# esp-proto-board.net
KiCad netlist of a schematic drawn in EAGLE
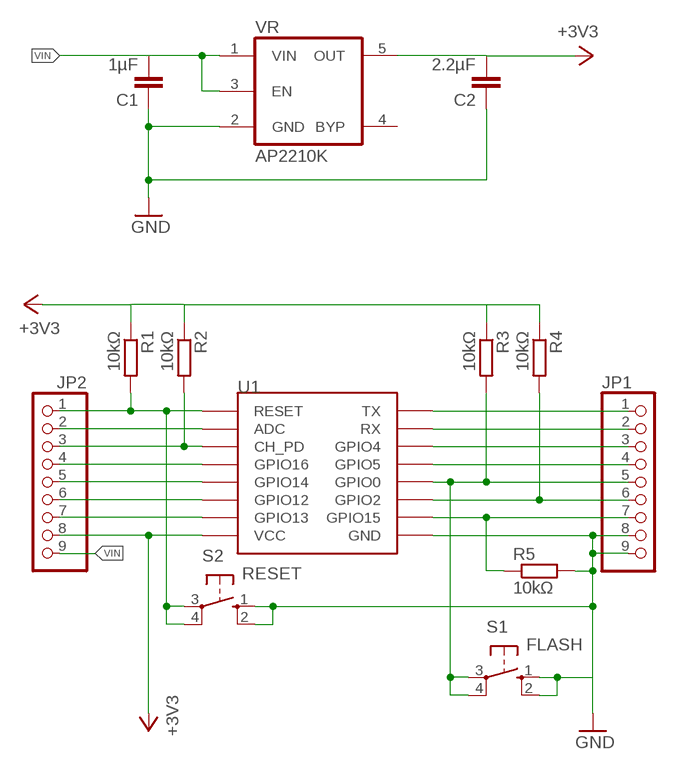
[diagram p0: schematic, sheet 1]

(export (version "E")
  (design (tool "Eeschema 10.0.6"))
  (components
    (comp (ref "C1")
      (value "1µF")
      (footprint "eagle-import:C0805K")
      (libsource (lib "eagle-import") (part "C-EUC0805K"))
    )
    (comp (ref "C2")
      (value "2.2µF")
      (footprint "eagle-import:C0805K")
      (libsource (lib "eagle-import") (part "C-EUC0805K"))
    )
    (comp (ref "JP1")
      (value "PINHD-1X9")
      (footprint "eagle-import:1X09")
      (libsource (lib "eagle-import") (part "PINHD-1X9"))
    )
    (comp (ref "JP2")
      (value "PINHD-1X9")
      (footprint "eagle-import:1X09")
      (libsource (lib "eagle-import") (part "PINHD-1X9"))
    )
    (comp (ref "R1")
      (value "10kΩ")
      (footprint "eagle-import:R0805W")
      (libsource (lib "eagle-import") (part "R-EU_R0805W"))
    )
    (comp (ref "R2")
      (value "10kΩ")
      (footprint "eagle-import:R0805W")
      (libsource (lib "eagle-import") (part "R-EU_R0805W"))
    )
    (comp (ref "R3")
      (value "10kΩ")
      (footprint "eagle-import:R0805W")
      (libsource (lib "eagle-import") (part "R-EU_R0805W"))
    )
    (comp (ref "R4")
      (value "10kΩ")
      (footprint "eagle-import:R0805W")
      (libsource (lib "eagle-import") (part "R-EU_R0805W"))
    )
    (comp (ref "R5")
      (value "10kΩ")
      (footprint "eagle-import:R0805W")
      (libsource (lib "eagle-import") (part "R-EU_R0805W"))
    )
    (comp (ref "S1")
      (value "FLASH")
      (footprint "eagle-import:B3F-10XX")
      (fields (field (name "MPN") "B3F-1000"))
      (libsource (lib "eagle-import") (part "10-XX"))
    )
    (comp (ref "S2")
      (value "RESET")
      (footprint "eagle-import:B3F-10XX")
      (fields (field (name "MPN") "B3F-1000"))
      (libsource (lib "eagle-import") (part "10-XX"))
    )
    (comp (ref "U1")
      (value "ESP12SMD")
      (footprint "eagle-import:ESP12-SMD")
      (libsource (lib "eagle-import") (part "ESP12SMD"))
    )
    (comp (ref "VR")
      (value "AP2210K")
      (footprint "eagle-import:SOT23-5")
      (libsource (lib "eagle-import") (part "AP2210K"))
    )
  )
  (nets
    (net (code "1") (name "+3V3") (class "Default")
      (node (ref "C2") (pin "2") (pinfunction "2_2") (pintype "passive"))
      (node (ref "JP2") (pin "8") (pinfunction "8_8") (pintype "passive"))
      (node (ref "R1") (pin "1") (pinfunction "1_1") (pintype "passive"))
      (node (ref "R2") (pin "1") (pinfunction "1_1") (pintype "passive"))
      (node (ref "R3") (pin "1") (pinfunction "1_1") (pintype "passive"))
      (node (ref "R4") (pin "1") (pinfunction "1_1") (pintype "passive"))
      (node (ref "U1") (pin "VCC") (pinfunction "VCC_VCC") (pintype "bidirectional"))
      (node (ref "VR") (pin "5") (pinfunction "OUT_5") (pintype "power_in"))
    )
    (net (code "2") (name "GND") (class "Default")
      (node (ref "C1") (pin "1") (pinfunction "1_1") (pintype "passive"))
      (node (ref "C2") (pin "1") (pinfunction "1_1") (pintype "passive"))
      (node (ref "JP1") (pin "8") (pinfunction "8_8") (pintype "passive"))
      (node (ref "JP1") (pin "9") (pinfunction "9_9") (pintype "passive"))
      (node (ref "R5") (pin "2") (pinfunction "2_2") (pintype "passive"))
      (node (ref "S1") (pin "1") (pinfunction "S_1") (pintype "passive"))
      (node (ref "S1") (pin "2") (pinfunction "S1_2") (pintype "passive"))
      (node (ref "S2") (pin "1") (pinfunction "S_1") (pintype "passive"))
      (node (ref "S2") (pin "2") (pinfunction "S1_2") (pintype "passive"))
      (node (ref "U1") (pin "GND") (pinfunction "GND_GND") (pintype "bidirectional"))
      (node (ref "VR") (pin "2") (pinfunction "GND_2") (pintype "power_in"))
    )
    (net (code "3") (name "Net-(JP1-Pad3)") (class "Default")
      (node (ref "JP1") (pin "3") (pinfunction "3_3") (pintype "passive"))
      (node (ref "U1") (pin "GPIO4") (pinfunction "GPIO4_GPIO4") (pintype "bidirectional"))
    )
    (net (code "4") (name "Net-(JP1-Pad4)") (class "Default")
      (node (ref "JP1") (pin "4") (pinfunction "4_4") (pintype "passive"))
      (node (ref "U1") (pin "GPIO5") (pinfunction "GPIO5_GPIO5") (pintype "bidirectional"))
    )
    (net (code "5") (name "Net-(JP1-Pad6)") (class "Default")
      (node (ref "JP1") (pin "6") (pinfunction "6_6") (pintype "passive"))
      (node (ref "R4") (pin "2") (pinfunction "2_2") (pintype "passive"))
      (node (ref "U1") (pin "GPIO2") (pinfunction "GPIO2_GPIO2") (pintype "bidirectional"))
    )
    (net (code "6") (name "Net-(JP1-Pad7)") (class "Default")
      (node (ref "JP1") (pin "7") (pinfunction "7_7") (pintype "passive"))
      (node (ref "R5") (pin "1") (pinfunction "1_1") (pintype "passive"))
      (node (ref "U1") (pin "GPIO15") (pinfunction "GPIO15_GPIO15") (pintype "bidirectional"))
    )
    (net (code "7") (name "Net-(JP2-Pad2)") (class "Default")
      (node (ref "JP2") (pin "2") (pinfunction "2_2") (pintype "passive"))
      (node (ref "U1") (pin "ADC") (pinfunction "ADC_ADC") (pintype "bidirectional"))
    )
    (net (code "8") (name "Net-(JP2-Pad3)") (class "Default")
      (node (ref "JP2") (pin "3") (pinfunction "3_3") (pintype "passive"))
      (node (ref "R2") (pin "2") (pinfunction "2_2") (pintype "passive"))
      (node (ref "U1") (pin "CH_PD") (pinfunction "CH_PD_CH_PD") (pintype "bidirectional"))
    )
    (net (code "9") (name "Net-(JP2-Pad4)") (class "Default")
      (node (ref "JP2") (pin "4") (pinfunction "4_4") (pintype "passive"))
      (node (ref "U1") (pin "GPIO16") (pinfunction "GPIO16_GPIO16") (pintype "bidirectional"))
    )
    (net (code "10") (name "Net-(JP2-Pad5)") (class "Default")
      (node (ref "JP2") (pin "5") (pinfunction "5_5") (pintype "passive"))
      (node (ref "U1") (pin "GPIO14") (pinfunction "GPIO14_GPIO14") (pintype "bidirectional"))
    )
    (net (code "11") (name "Net-(JP2-Pad6)") (class "Default")
      (node (ref "JP2") (pin "6") (pinfunction "6_6") (pintype "passive"))
      (node (ref "U1") (pin "GPIO12") (pinfunction "GPIO12_GPIO12") (pintype "bidirectional"))
    )
    (net (code "12") (name "Net-(JP2-Pad7)") (class "Default")
      (node (ref "JP2") (pin "7") (pinfunction "7_7") (pintype "passive"))
      (node (ref "U1") (pin "GPIO13") (pinfunction "GPIO13_GPIO13") (pintype "bidirectional"))
    )
    (net (code "13") (name "Net-(S1-P)") (class "Default")
      (node (ref "JP1") (pin "5") (pinfunction "5_5") (pintype "passive"))
      (node (ref "R3") (pin "2") (pinfunction "2_2") (pintype "passive"))
      (node (ref "S1") (pin "3") (pinfunction "P_3") (pintype "passive"))
      (node (ref "S1") (pin "4") (pinfunction "P1_4") (pintype "passive"))
      (node (ref "U1") (pin "GPIO0") (pinfunction "GPIO0_GPIO0") (pintype "bidirectional"))
    )
    (net (code "14") (name "Net-(S2-P)") (class "Default")
      (node (ref "JP2") (pin "1") (pinfunction "1_1") (pintype "passive"))
      (node (ref "R1") (pin "2") (pinfunction "2_2") (pintype "passive"))
      (node (ref "S2") (pin "3") (pinfunction "P_3") (pintype "passive"))
      (node (ref "S2") (pin "4") (pinfunction "P1_4") (pintype "passive"))
      (node (ref "U1") (pin "RESET") (pinfunction "RESET_RESET") (pintype "bidirectional"))
    )
    (net (code "15") (name "Net-(U1-RX)") (class "Default")
      (node (ref "JP1") (pin "2") (pinfunction "2_2") (pintype "passive"))
      (node (ref "U1") (pin "RXD0") (pinfunction "RX_RXD0") (pintype "bidirectional"))
    )
    (net (code "16") (name "Net-(U1-TX)") (class "Default")
      (node (ref "JP1") (pin "1") (pinfunction "1_1") (pintype "passive"))
      (node (ref "U1") (pin "TXD0") (pinfunction "TX_TXD0") (pintype "bidirectional"))
    )
    (net (code "17") (name "VIN") (class "Default")
      (node (ref "C1") (pin "2") (pinfunction "2_2") (pintype "passive"))
      (node (ref "JP2") (pin "9") (pinfunction "9_9") (pintype "passive"))
      (node (ref "VR") (pin "1") (pinfunction "VIN_1") (pintype "input"))
      (node (ref "VR") (pin "3") (pinfunction "EN_3") (pintype "input"))
    )
    (net (code "18") (name "unconnected-(VR-BYP-Pad4)") (class "Default")
      (node (ref "VR") (pin "4") (pinfunction "BYP_4") (pintype "output"))
    )
  )
)
